# Schematic.net
KiCad netlist of a schematic drawn in EasyEDA
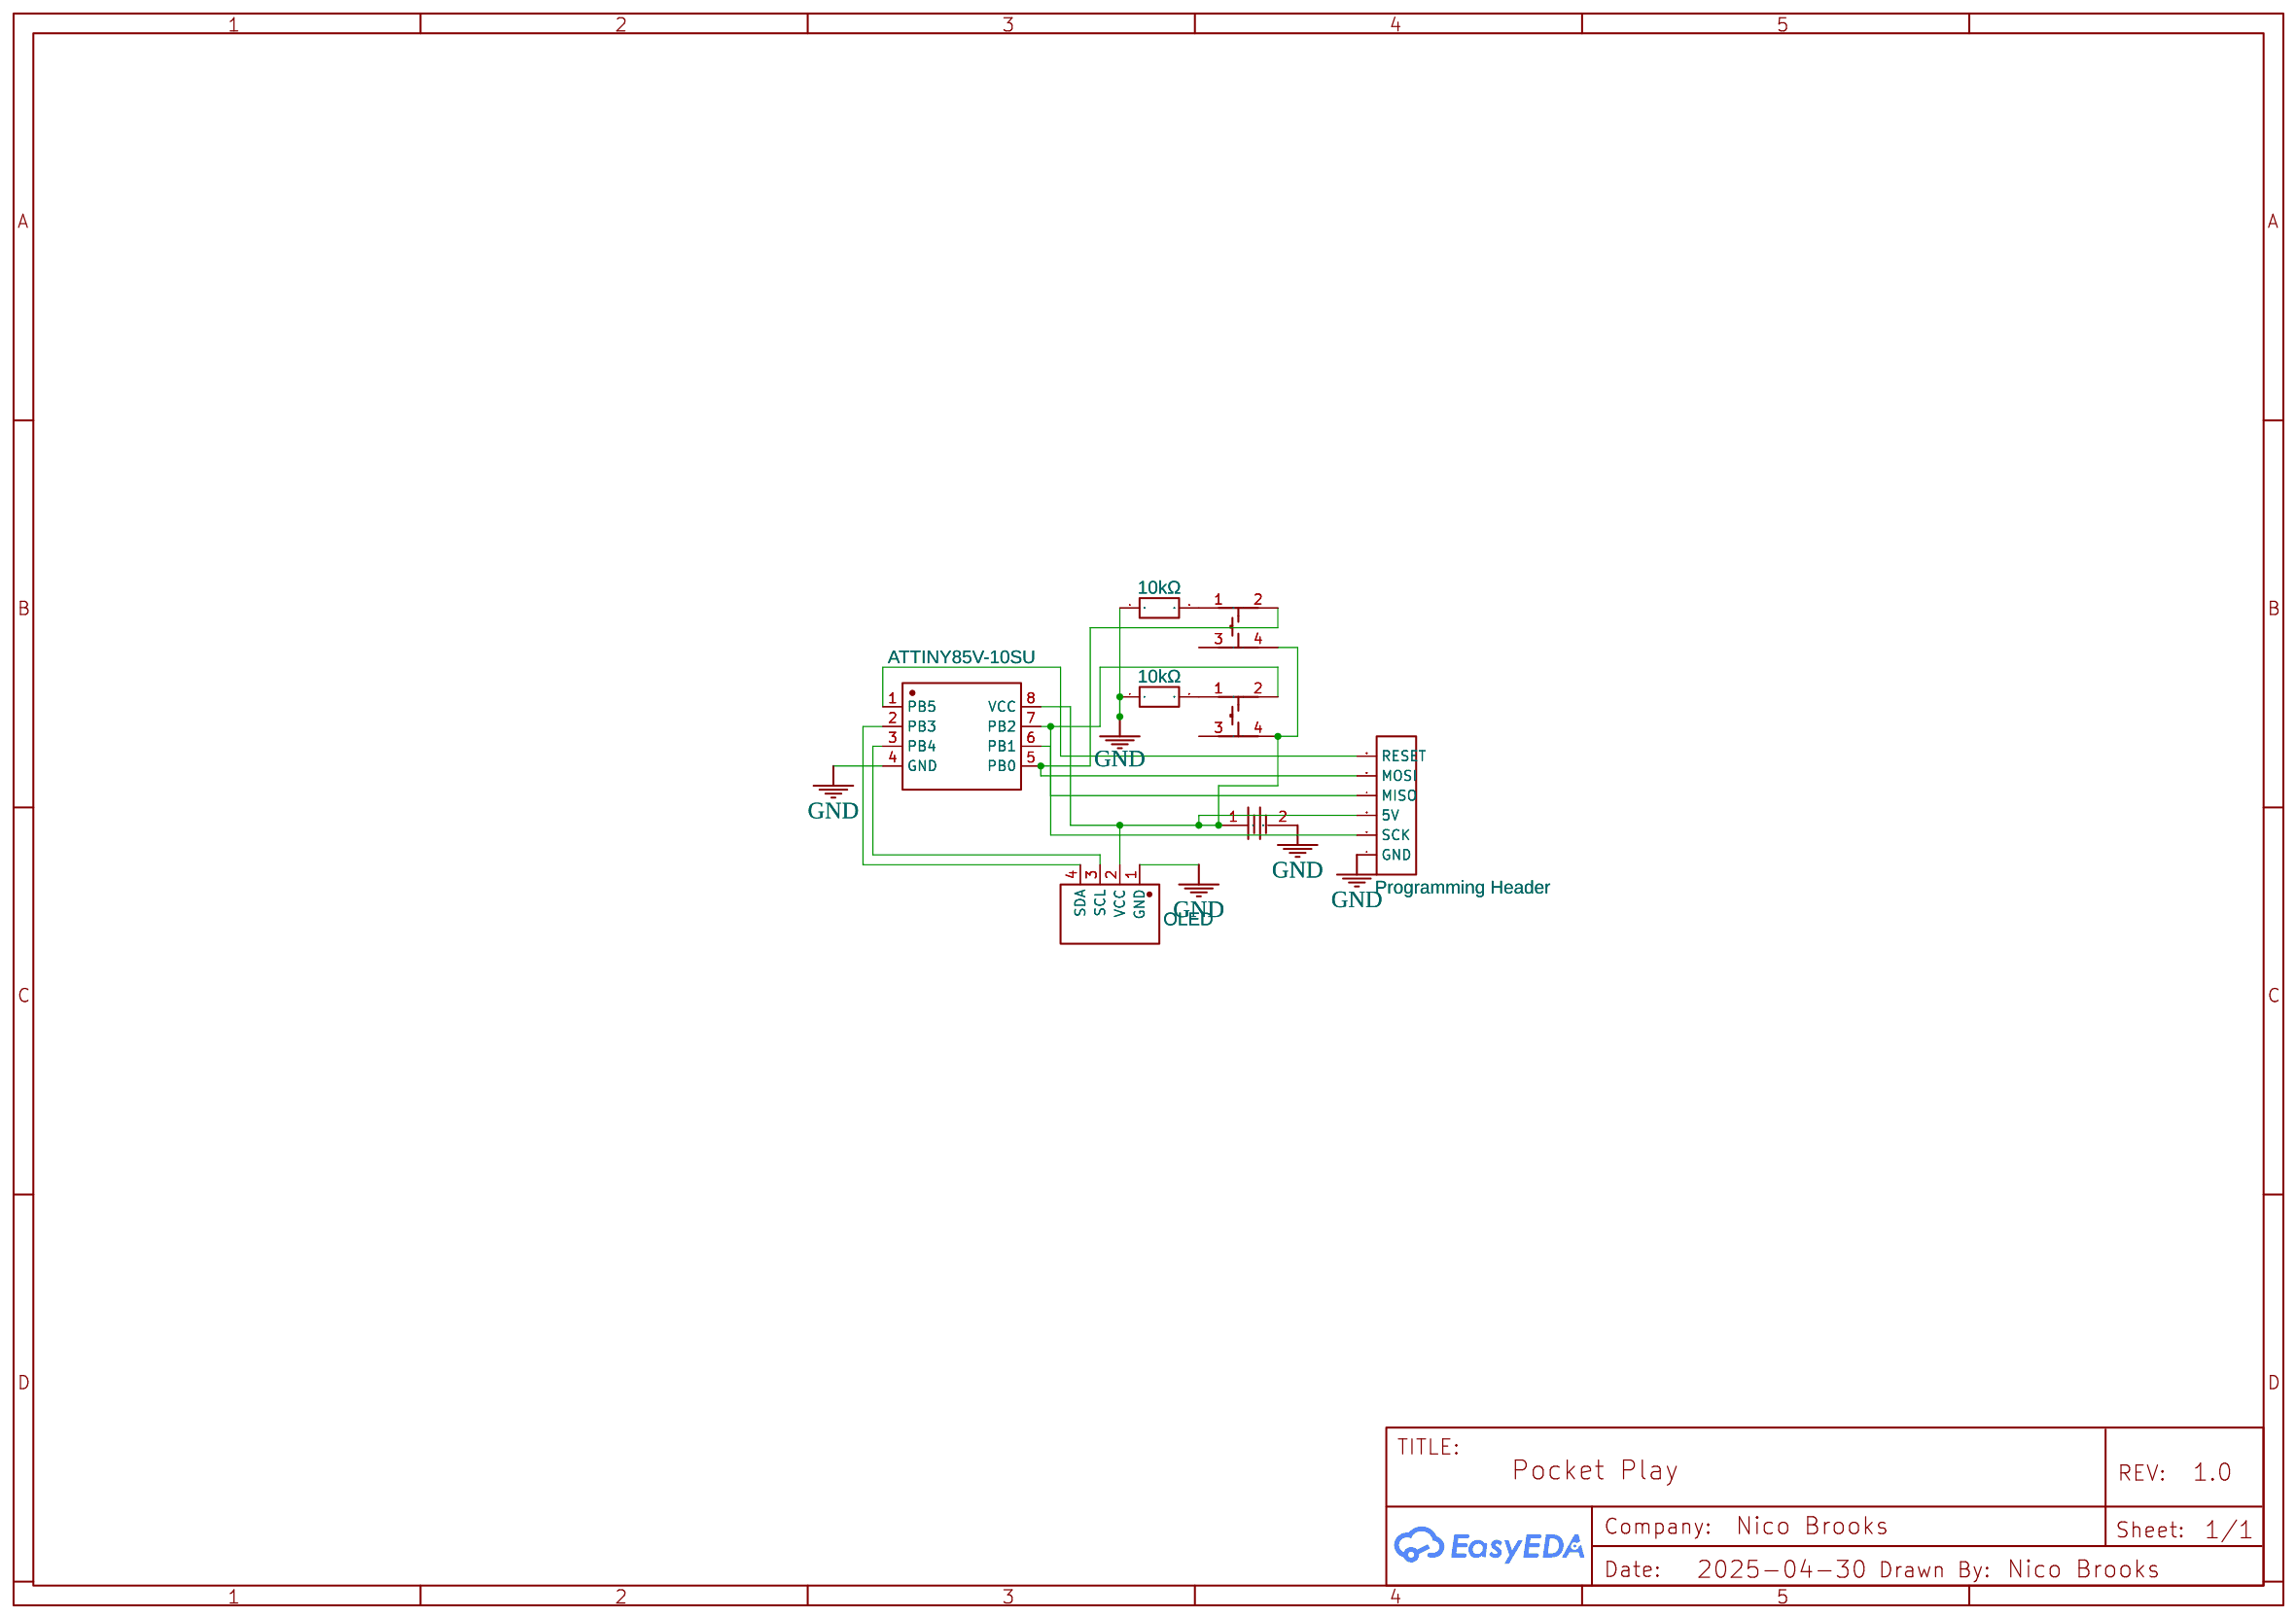
[diagram p0: schematic sheet]

(export (version "E")
  (design (tool "Eeschema 10.0.6"))
  (components
    (comp (ref "B1")
      (value "CR2032")
      (fields (field (name "Manufacturer Part") "CR2032-BS-6-1") (field (name "Manufacturer") "Q&J"))
      (libsource (lib "") (part "CR2032-BS-6-1"))
    )
    (comp (ref "J1") (value "Programming Header") (libsource (lib "") (part "HEADER_6")))
    (comp (ref "OLED1")
      (value "OLED")
      (fields (field (name "Manufacturer Part") "UN-2864KMBEG01"))
      (libsource (lib "") (part "UN-2864KMBEG01"))
    )
    (comp (ref "U1")
      (value "10kΩ")
      (fields (field (name "Manufacturer Part") "CR1/4W-10K±5%-OT26") (field (name "Manufacturer") "VO(翔胜)"))
      (libsource (lib "") (part "CR1/4W-10K±5%-OT26"))
    )
    (comp (ref "U2")
      (value "10kΩ")
      (fields (field (name "Manufacturer Part") "CR1/4W-10K±5%-OT26") (field (name "Manufacturer") "VO(翔胜)"))
      (libsource (lib "") (part "CR1/4W-10K±5%-OT26"))
    )
    (comp (ref "U4")
      (value "Left Button")
      (fields
        (field (name "Manufacturer Part") "ZX-QC1212-8.0TP")
        (field (name "Manufacturer") "Megastar(兆星)")
      )
      (libsource (lib "") (part "ZX-QC1212-8.0TP"))
    )
    (comp (ref "U5")
      (value "Right Button")
      (fields
        (field (name "Manufacturer Part") "ZX-QC1212-8.0TP")
        (field (name "Manufacturer") "Megastar(兆星)")
      )
      (libsource (lib "") (part "ZX-QC1212-8.0TP"))
    )
    (comp (ref "U6")
      (value "ATTINY85V-10SU")
      (fields (field (name "Manufacturer") "MICROCHIP(美国微芯)"))
      (libsource (lib "") (part "ATTINY85V-10SU"))
    )
  )
  (nets
    (net (code "1") (name "GND") (class "Default")
      (node (ref "B1") (pin "2") (pinfunction "2_2") (pintype "input"))
      (node (ref "J1") (pin "1") (pinfunction "GND_1") (pintype "input"))
      (node (ref "OLED1") (pin "1") (pinfunction "GND_1") (pintype "unspecified"))
      (node (ref "U1") (pin "1") (pinfunction "1_1") (pintype "unspecified"))
      (node (ref "U2") (pin "1") (pinfunction "1_1") (pintype "unspecified"))
      (node (ref "U6") (pin "4") (pinfunction "GND_4") (pintype "unspecified"))
    )
    (net (code "2") (name "Net-(J1-5V)") (class "Default")
      (node (ref "B1") (pin "1") (pinfunction "1_1") (pintype "input"))
      (node (ref "J1") (pin "3") (pinfunction "5V_3") (pintype "input"))
      (node (ref "OLED1") (pin "2") (pinfunction "VCC_2") (pintype "unspecified"))
      (node (ref "U4") (pin "4") (pinfunction "4_4") (pintype "unspecified"))
      (node (ref "U5") (pin "4") (pinfunction "4_4") (pintype "unspecified"))
      (node (ref "U6") (pin "8") (pinfunction "VCC_8") (pintype "unspecified"))
    )
    (net (code "3") (name "Net-(J1-MISO)") (class "Default")
      (node (ref "J1") (pin "4") (pinfunction "MISO_4") (pintype "input"))
      (node (ref "U6") (pin "6") (pinfunction "PB1_6") (pintype "unspecified"))
    )
    (net (code "4") (name "Net-(J1-MOSI)") (class "Default")
      (node (ref "J1") (pin "5") (pinfunction "MOSI_5") (pintype "input"))
      (node (ref "U4") (pin "2") (pinfunction "2_2") (pintype "unspecified"))
      (node (ref "U6") (pin "5") (pinfunction "PB0_5") (pintype "unspecified"))
    )
    (net (code "5") (name "Net-(J1-RESET)") (class "Default")
      (node (ref "J1") (pin "6") (pinfunction "RESET_6") (pintype "input"))
      (node (ref "U6") (pin "1") (pinfunction "PB5_1") (pintype "unspecified"))
    )
    (net (code "6") (name "Net-(J1-SCK)") (class "Default")
      (node (ref "J1") (pin "2") (pinfunction "SCK_2") (pintype "input"))
      (node (ref "U5") (pin "2") (pinfunction "2_2") (pintype "unspecified"))
      (node (ref "U6") (pin "7") (pinfunction "PB2_7") (pintype "unspecified"))
    )
    (net (code "7") (name "Net-(OLED1-SCL)") (class "Default")
      (node (ref "OLED1") (pin "3") (pinfunction "SCL_3") (pintype "unspecified"))
      (node (ref "U6") (pin "3") (pinfunction "PB4_3") (pintype "unspecified"))
    )
    (net (code "8") (name "Net-(OLED1-SDA)") (class "Default")
      (node (ref "OLED1") (pin "4") (pinfunction "SDA_4") (pintype "unspecified"))
      (node (ref "U6") (pin "2") (pinfunction "PB3_2") (pintype "unspecified"))
    )
    (net (code "9") (name "Net-(U1-Pad2)") (class "Default")
      (node (ref "U1") (pin "2") (pinfunction "2_2") (pintype "unspecified"))
      (node (ref "U4") (pin "1") (pinfunction "1_1") (pintype "unspecified"))
    )
    (net (code "10") (name "Net-(U2-Pad2)") (class "Default")
      (node (ref "U2") (pin "2") (pinfunction "2_2") (pintype "unspecified"))
      (node (ref "U5") (pin "1") (pinfunction "1_1") (pintype "unspecified"))
    )
    (net (code "11") (name "unconnected-(U4-Pad3)") (class "Default")
      (node (ref "U4") (pin "3") (pinfunction "3_3") (pintype "unspecified"))
    )
    (net (code "12") (name "unconnected-(U5-Pad3)") (class "Default")
      (node (ref "U5") (pin "3") (pinfunction "3_3") (pintype "unspecified"))
    )
  )
)
